# PSU.net
KiCad netlist of a schematic drawn in Altium Designer
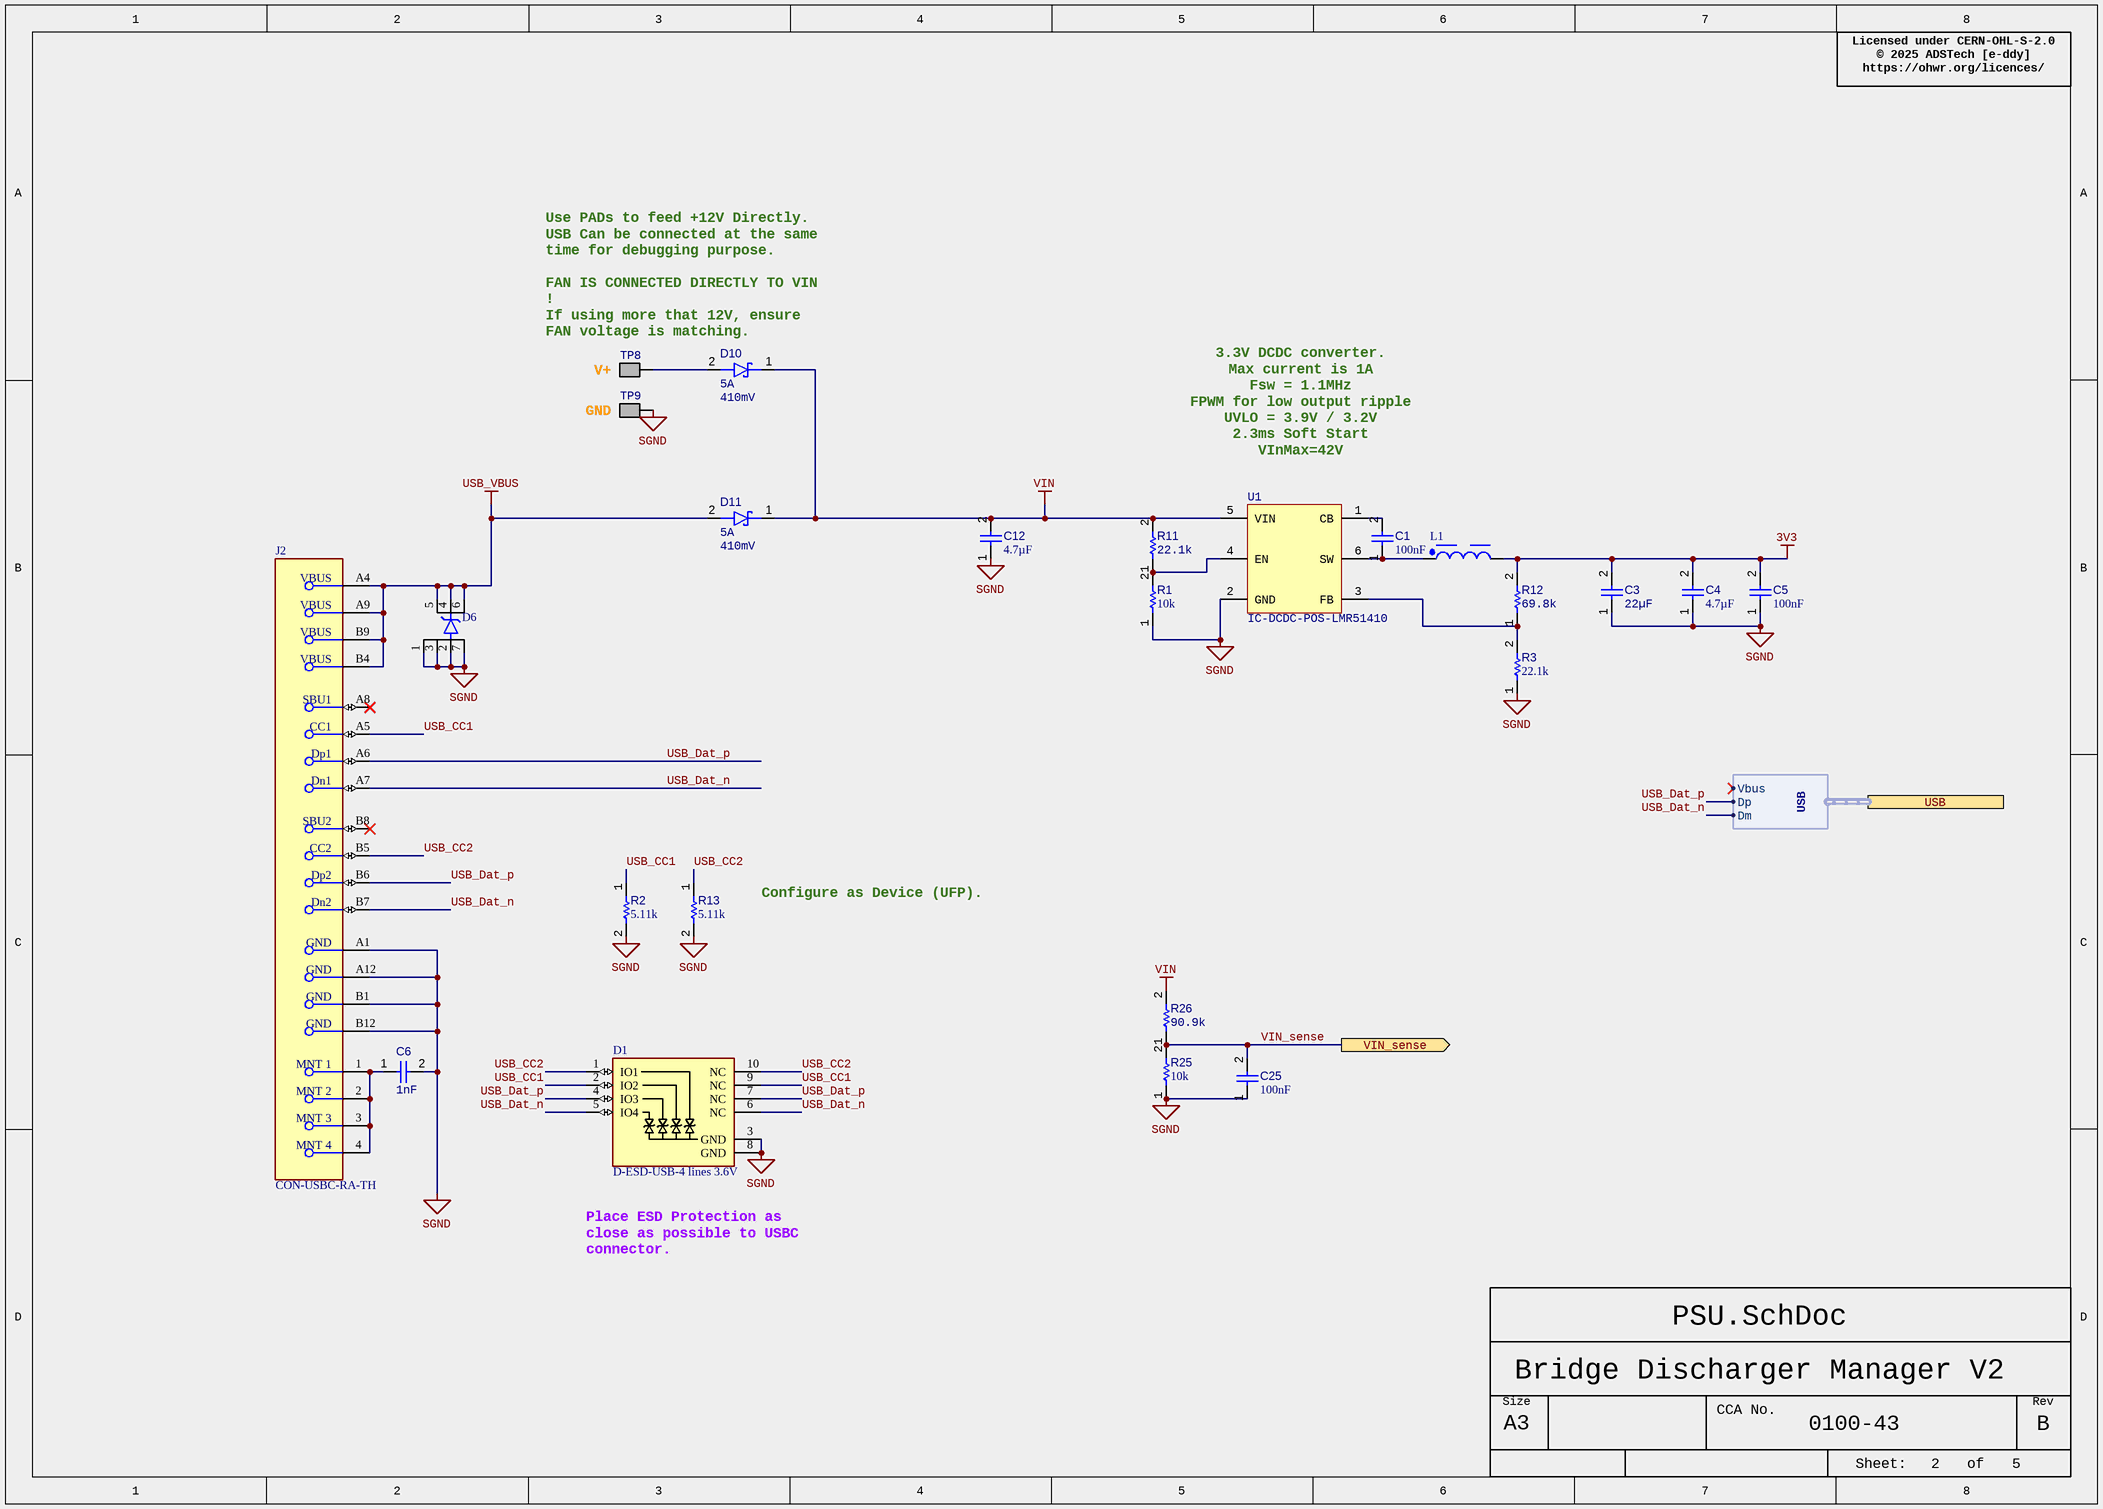
[diagram p0: PSU.SchDoc]

(export (version "E")
  (design (tool "Eeschema 10.0.6"))
  (components
    (comp (ref "C1")
      (value "100nF")
      (footprint "CAP_0402-IPC_B")
      (description "Multilayer Ceramic Capacitor, 0.1 uF, 50 V, ± 10%, X7R, 0402 [1005 Metric]")
      (fields (field (name "TOLERANCE") "10%") (field (name "Comment") "C-0402-CER-X7R-100nF-10%-50V"))
      (libsource (lib "FIME Lille") (part "CAP-NP-2"))
    )
    (comp (ref "C3")
      (value "22µF")
      (footprint "FP-GRM21B-0_2-e0_2_0_7-MFG")
      (fields (field (name "Comment") "C-0805-CER-X5R-22µF-25V"))
      (libsource (lib "FIME Lille") (part "CAP-NP-2"))
    )
    (comp (ref "C4")
      (value "4.7µF")
      (footprint "FP-C2012X7R1H475K125AC-IPC_B")
      (fields (field (name "Comment") "C-0805-CER-X7R-4,7µF-10%-50V"))
      (libsource (lib "FIME Lille") (part "CAP-NP-2"))
    )
    (comp (ref "C5")
      (value "100nF")
      (footprint "CAP_0402-IPC_B")
      (description "Multilayer Ceramic Capacitor, 0.1 uF, 50 V, ± 10%, X7R, 0402 [1005 Metric]")
      (fields (field (name "TOLERANCE") "10%") (field (name "Comment") "C-0402-CER-X7R-100nF-10%-50V"))
      (libsource (lib "FIME Lille") (part "CAP-NP-2"))
    )
    (comp (ref "C6")
      (value "1nF")
      (footprint "CAP-1206-IPC_B")
      (fields (field (name "Comment") "C-1206-CER-X7R-1nF-10%-1kV"))
      (libsource (lib "FIME Lille") (part "CAP-NP-2"))
    )
    (comp (ref "C12")
      (value "4.7µF")
      (footprint "FP-C2012X7R1H475K125AC-IPC_B")
      (fields (field (name "Comment") "C-0805-CER-X7R-4,7µF-10%-50V"))
      (libsource (lib "FIME Lille") (part "CAP-NP-2"))
    )
    (comp (ref "C25")
      (value "100nF")
      (footprint "CAP_0402-IPC_B")
      (description "Multilayer Ceramic Capacitor, 0.1 uF, 50 V, ± 10%, X7R, 0402 [1005 Metric]")
      (fields (field (name "TOLERANCE") "10%") (field (name "Comment") "C-0402-CER-X7R-100nF-10%-50V"))
      (libsource (lib "FIME Lille") (part "CAP-NP-2"))
    )
    (comp (ref "D1")
      (value "D-ESD-USB-4 lines 3.6V")
      (footprint "FP-DQA0010A-MFG")
      (description "Trans Voltage Suppressor Diode, 17W, 3.6V V(RWM), Bidirectional, 4 Element, Silicon")
      (libsource (lib "FIME Lille") (part "a9d36efb1c7e747d1fd0d56c7ea0961"))
    )
    (comp (ref "D6")
      (value "D-TVS-14V-TVS1400DRVR")
      (footprint "FP-DRV0006A-MFG")
      (description "Trans Voltage Suppressor Diode, 14V V(RWM), Unidirectional, Silicon")
      (libsource (lib "FIME Lille") (part "05871d3186a2232acfb1f4d5e814824"))
    )
    (comp (ref "D10")
      (value "D-SCH-VSSAF5N50-DO-221AD-2-5A-50V")
      (footprint "FP-S8-V-3915_01-001-CATHO-MFG")
      (description "Rectifier Diode, Schottky, 1 Phase, 1 Element, 5A, 50V V(RRM), Silicon, DO-221AC")
      (fields (field (name "FORWARD CURRENT") "5A") (field (name "FORWARD VOLTAGE") "410mV"))
      (libsource (lib "FIME Lille") (part "DIODE-SKY-2"))
    )
    (comp (ref "D11")
      (value "D-SCH-VSSAF5N50-DO-221AD-2-5A-50V")
      (footprint "FP-S8-V-3915_01-001-CATHO-MFG")
      (description "Rectifier Diode, Schottky, 1 Phase, 1 Element, 5A, 50V V(RRM), Silicon, DO-221AC")
      (fields (field (name "FORWARD CURRENT") "5A") (field (name "FORWARD VOLTAGE") "410mV"))
      (libsource (lib "FIME Lille") (part "DIODE-SKY-2"))
    )
    (comp (ref "J2")
      (value "CON-USBC-RA-TH")
      (footprint "FP-USB4085-GF-A-MFG")
      (description "USB Connector, 16 Contact(s), Female, Right Angle, Solder Terminal, Receptacle")
      (libsource (lib "FIME Lille") (part "10fa745527c8b974685cbca3c197132"))
    )
    (comp (ref "L1")
      (value "L-2424-22uH-2.1A-74404064220")
      (footprint "WE-LQS_6045")
      (description "General Purpose Inductor, 22uH, 20%, 1 Element, SMD, 2424")
      (fields (field (name "TOLERANCE") "20%"))
      (libsource (lib "FIME Lille") (part "Inductor - 2"))
    )
    (comp (ref "R1")
      (value "10k")
      (footprint "RES-0402-IPC_B")
      (description "0402 10000.0 Ω 1% 100ppm 0.063W Resistor")
      (fields (field (name "MPN") "RC0402FR-0710KL") (field (name "TOLERANCE") "1%"))
      (libsource (lib "FIME Lille") (part "RES-2"))
    )
    (comp (ref "R2")
      (value "5.11k")
      (footprint "RES-0402-IPC_B")
      (description "0402 5110.0 Ω 1% 100ppm 0.063W Resistor")
      (fields (field (name "POWER") "63mW") (field (name "TOLERANCE") "1%"))
      (libsource (lib "FIME Lille") (part "RES-2"))
    )
    (comp (ref "R3")
      (value "22.1k")
      (footprint "RES-0402-IPC_B")
      (description "0402 22100.0 Ω 1% 100ppm 0.063W Resistor")
      (fields (field (name "MPN") "CRCW040222K1FKED") (field (name "TOLERANCE") "1%"))
      (libsource (lib "FIME Lille") (part "RES-2"))
    )
    (comp (ref "R11")
      (value "22.1k")
      (footprint "RES-0402-IPC_B")
      (description "0402 22100.0 Ω 1% 100ppm 0.063W Resistor")
      (fields (field (name "MPN") "CRCW040222K1FKED") (field (name "POWER") "63mW"))
      (libsource (lib "FIME Lille") (part "RES-2"))
    )
    (comp (ref "R12")
      (value "69.8k")
      (footprint "RES-0402-IPC_B")
      (description "0402 69800.0 Ω 0.1% 25ppm 0.016W Resistor")
      (fields (field (name "POWER") "16mW") (field (name "TOLERANCE") "0.1"))
      (libsource (lib "FIME Lille") (part "RES-2"))
    )
    (comp (ref "R13")
      (value "5.11k")
      (footprint "RES-0402-IPC_B")
      (description "0402 5110.0 Ω 1% 100ppm 0.063W Resistor")
      (fields (field (name "POWER") "63mW") (field (name "TOLERANCE") "1%"))
      (libsource (lib "FIME Lille") (part "RES-2"))
    )
    (comp (ref "R25")
      (value "10k")
      (footprint "RES-0402-IPC_B")
      (description "0402 10000.0 Ω 1% 100ppm 0.063W Resistor")
      (fields (field (name "POWER") "63mW") (field (name "MPN") "RC0402FR-0710KL"))
      (libsource (lib "FIME Lille") (part "RES-2"))
    )
    (comp (ref "R26")
      (value "90.9k")
      (footprint "RES-0402-IPC_B")
      (description "0402 90900.0 Ω 1% 100ppm 0.063W Resistor")
      (fields (field (name "POWER") "63mW") (field (name "MPN") "CRCW040290K9FKED"))
      (libsource (lib "FIME Lille") (part "RES-2"))
    )
    (comp (ref "TP8")
      (value "SMT-PAD-3x2")
      (footprint "3x2 pad")
      (description "3x2mm standard pad for wire soldering")
      (fields (field (name "NAME") "V+"))
      (libsource (lib "FIME Lille") (part "Copy of Test point"))
    )
    (comp (ref "TP9")
      (value "SMT-PAD-3x2")
      (footprint "3x2 pad")
      (description "3x2mm standard pad for wire soldering")
      (fields (field (name "NAME") "GND"))
      (libsource (lib "FIME Lille") (part "Copy of Test point"))
    )
    (comp (ref "U1")
      (value "IC-DCDC-POS-LMR51410")
      (footprint "ETA-SOT23-6_N")
      (description "SIMPLE SWITCHER® 4V to 42V, 1A synchronous buck converter with 26.5uA IQ 6-SOT-23 -40 to 150")
      (libsource (lib "FIME Lille") (part "LMR51410YFDBVR-Symbol-1"))
    )
  )
  (nets
    (net (code "2") (name "/USB_CC1") (class "Default")
      (node (ref "D1") (pin "2") (pinfunction "IO2_2") (pintype "bidirectional"))
      (node (ref "D1") (pin "9") (pinfunction "NC_9") (pintype "passive"))
      (node (ref "J2") (pin "A5") (pinfunction "CC1_A5") (pintype "bidirectional"))
      (node (ref "R2") (pin "1") (pinfunction "1_1") (pintype "passive"))
    )
    (net (code "3") (name "/USB_CC2") (class "Default")
      (node (ref "D1") (pin "1") (pinfunction "IO1_1") (pintype "bidirectional"))
      (node (ref "D1") (pin "10") (pinfunction "NC_10") (pintype "passive"))
      (node (ref "J2") (pin "B5") (pinfunction "CC2_B5") (pintype "bidirectional"))
      (node (ref "R13") (pin "1") (pinfunction "1_1") (pintype "passive"))
    )
    (net (code "4") (name "/USB_Dat_n") (class "Default")
      (node (ref "D1") (pin "5") (pinfunction "IO4_5") (pintype "bidirectional"))
      (node (ref "D1") (pin "6") (pinfunction "NC_6") (pintype "passive"))
      (node (ref "J2") (pin "A7") (pinfunction "Dn1_A7") (pintype "bidirectional"))
      (node (ref "J2") (pin "B7") (pinfunction "Dn2_B7") (pintype "bidirectional"))
    )
    (net (code "5") (name "/USB_Dat_p") (class "Default")
      (node (ref "D1") (pin "4") (pinfunction "IO3_4") (pintype "bidirectional"))
      (node (ref "D1") (pin "7") (pinfunction "NC_7") (pintype "passive"))
      (node (ref "J2") (pin "A6") (pinfunction "Dp1_A6") (pintype "bidirectional"))
      (node (ref "J2") (pin "B6") (pinfunction "Dp2_B6") (pintype "bidirectional"))
    )
    (net (code "6") (name "/VIN_sense") (class "Default")
      (node (ref "C25") (pin "2") (pinfunction "2_2") (pintype "passive"))
      (node (ref "R25") (pin "2") (pinfunction "2_2") (pintype "passive"))
      (node (ref "R26") (pin "1") (pinfunction "1_1") (pintype "passive"))
    )
    (net (code "8") (name "3V3") (class "Default")
      (node (ref "C3") (pin "2") (pinfunction "2_2") (pintype "passive"))
      (node (ref "C4") (pin "2") (pinfunction "2_2") (pintype "passive"))
      (node (ref "C5") (pin "2") (pinfunction "2_2") (pintype "passive"))
      (node (ref "L1") (pin "2") (pinfunction "2_2") (pintype "passive"))
      (node (ref "R12") (pin "2") (pinfunction "2_2") (pintype "passive"))
    )
    (net (code "9") (name "Net-(D10-A)") (class "Default")
      (node (ref "D10") (pin "2") (pinfunction "A_2") (pintype "passive"))
      (node (ref "TP8") (pin "1") (pinfunction "1_1") (pintype "passive"))
    )
    (net (code "10") (name "Net-(J2-MNT_1)") (class "Default")
      (node (ref "C6") (pin "1") (pinfunction "1_1") (pintype "passive"))
      (node (ref "J2") (pin "1") (pinfunction "MNT_1_1") (pintype "passive"))
      (node (ref "J2") (pin "2") (pinfunction "MNT_2_2") (pintype "passive"))
      (node (ref "J2") (pin "3") (pinfunction "MNT_3_3") (pintype "passive"))
      (node (ref "J2") (pin "4") (pinfunction "MNT_4_4") (pintype "passive"))
    )
    (net (code "11") (name "Net-(U1-CB)") (class "Default")
      (node (ref "C1") (pin "2") (pinfunction "2_2") (pintype "passive"))
      (node (ref "U1") (pin "1") (pinfunction "CB_1") (pintype "passive"))
    )
    (net (code "12") (name "Net-(U1-EN)") (class "Default")
      (node (ref "R1") (pin "2") (pinfunction "2_2") (pintype "passive"))
      (node (ref "R11") (pin "1") (pinfunction "1_1") (pintype "passive"))
      (node (ref "U1") (pin "4") (pinfunction "EN_4") (pintype "passive"))
    )
    (net (code "13") (name "Net-(U1-FB)") (class "Default")
      (node (ref "R12") (pin "1") (pinfunction "1_1") (pintype "passive"))
      (node (ref "R3") (pin "2") (pinfunction "2_2") (pintype "passive"))
      (node (ref "U1") (pin "3") (pinfunction "FB_3") (pintype "passive"))
    )
    (net (code "14") (name "Net-(U1-SW)") (class "Default")
      (node (ref "C1") (pin "1") (pinfunction "1_1") (pintype "passive"))
      (node (ref "L1") (pin "1") (pinfunction "1_1") (pintype "passive"))
      (node (ref "U1") (pin "6") (pinfunction "SW_6") (pintype "passive"))
    )
    (net (code "15") (name "SGND") (class "Default")
      (node (ref "C12") (pin "1") (pinfunction "1_1") (pintype "passive"))
      (node (ref "C25") (pin "1") (pinfunction "1_1") (pintype "passive"))
      (node (ref "C3") (pin "1") (pinfunction "1_1") (pintype "passive"))
      (node (ref "C4") (pin "1") (pinfunction "1_1") (pintype "passive"))
      (node (ref "C5") (pin "1") (pinfunction "1_1") (pintype "passive"))
      (node (ref "C6") (pin "2") (pinfunction "2_2") (pintype "passive"))
      (node (ref "D1") (pin "3") (pinfunction "GND_3") (pintype "power_in"))
      (node (ref "D1") (pin "8") (pinfunction "GND_8") (pintype "power_in"))
      (node (ref "D6") (pin "1") (pinfunction "GND_1") (pintype "power_in"))
      (node (ref "D6") (pin "2") (pinfunction "GND_2") (pintype "power_in"))
      (node (ref "D6") (pin "3") (pinfunction "GND_3") (pintype "power_in"))
      (node (ref "D6") (pin "7") (pinfunction "GND_7") (pintype "power_in"))
      (node (ref "J2") (pin "A1") (pinfunction "GND_A1") (pintype "power_in"))
      (node (ref "J2") (pin "A12") (pinfunction "GND_A12") (pintype "power_in"))
      (node (ref "J2") (pin "B1") (pinfunction "GND_B1") (pintype "power_in"))
      (node (ref "J2") (pin "B12") (pinfunction "GND_B12") (pintype "power_in"))
      (node (ref "R1") (pin "1") (pinfunction "1_1") (pintype "passive"))
      (node (ref "R13") (pin "2") (pinfunction "2_2") (pintype "passive"))
      (node (ref "R2") (pin "2") (pinfunction "2_2") (pintype "passive"))
      (node (ref "R25") (pin "1") (pinfunction "1_1") (pintype "passive"))
      (node (ref "R3") (pin "1") (pinfunction "1_1") (pintype "passive"))
      (node (ref "TP9") (pin "1") (pinfunction "1_1") (pintype "passive"))
      (node (ref "U1") (pin "2") (pinfunction "GND_2") (pintype "passive"))
    )
    (net (code "16") (name "USB_VBUS") (class "Default")
      (node (ref "D11") (pin "2") (pinfunction "A_2") (pintype "passive"))
      (node (ref "D6") (pin "4") (pinfunction "IN_4") (pintype "passive"))
      (node (ref "D6") (pin "5") (pinfunction "IN_5") (pintype "passive"))
      (node (ref "D6") (pin "6") (pinfunction "IN_6") (pintype "passive"))
      (node (ref "J2") (pin "A4") (pinfunction "VBUS_A4") (pintype "power_in"))
      (node (ref "J2") (pin "A9") (pinfunction "VBUS_A9") (pintype "power_in"))
      (node (ref "J2") (pin "B4") (pinfunction "VBUS_B4") (pintype "power_in"))
      (node (ref "J2") (pin "B9") (pinfunction "VBUS_B9") (pintype "power_in"))
    )
    (net (code "17") (name "VIN") (class "Default")
      (node (ref "C12") (pin "2") (pinfunction "2_2") (pintype "passive"))
      (node (ref "D10") (pin "1") (pinfunction "K_1") (pintype "passive"))
      (node (ref "D11") (pin "1") (pinfunction "K_1") (pintype "passive"))
      (node (ref "R11") (pin "2") (pinfunction "2_2") (pintype "passive"))
      (node (ref "R26") (pin "2") (pinfunction "2_2") (pintype "passive"))
      (node (ref "U1") (pin "5") (pinfunction "VIN_5") (pintype "passive"))
    )
    (net (code "18") (name "unconnected-(J2-SBU1-PadA8)") (class "Default")
      (node (ref "J2") (pin "A8") (pinfunction "SBU1_A8") (pintype "bidirectional+no_connect"))
    )
    (net (code "19") (name "unconnected-(J2-SBU2-PadB8)") (class "Default")
      (node (ref "J2") (pin "B8") (pinfunction "SBU2_B8") (pintype "bidirectional+no_connect"))
    )
  )
)
